# Sheet1-MCU.net
KiCad netlist of a schematic drawn in Altium Designer
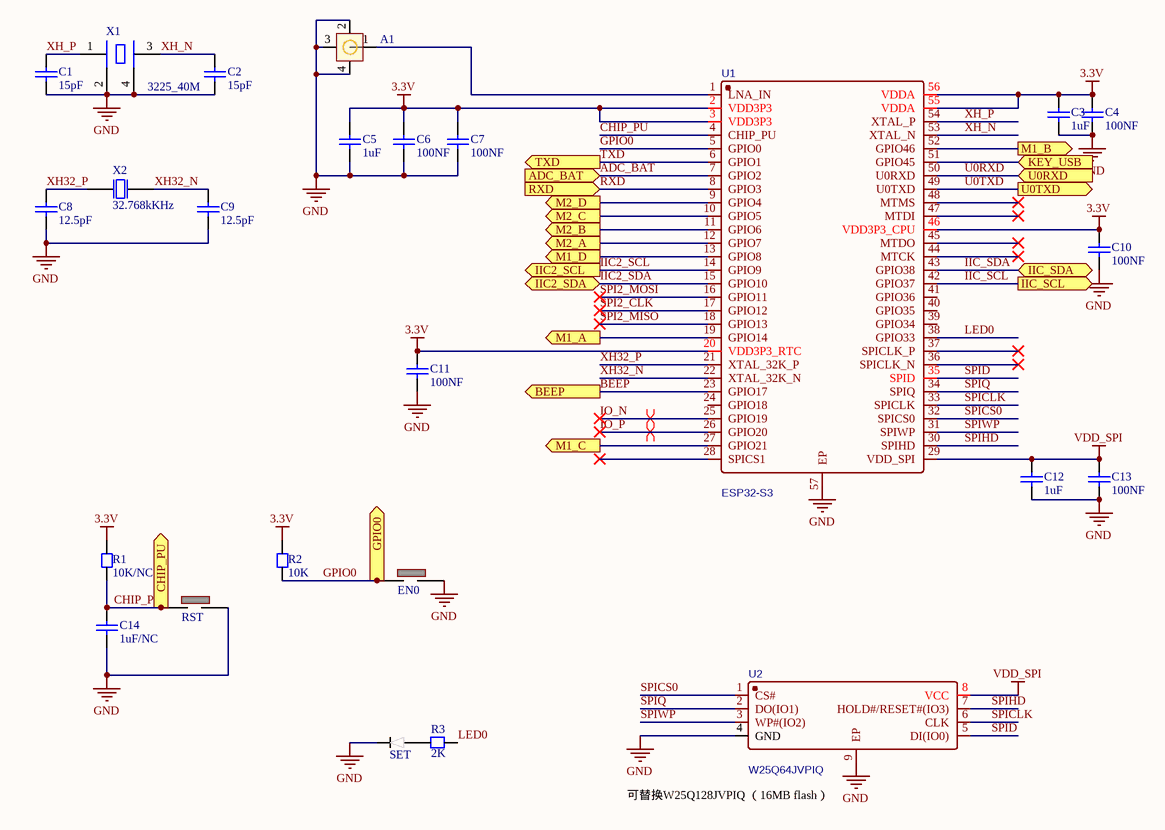
[diagram p0: Sheet1-MCU.SchDoc]

(export (version "E")
  (design (tool "Eeschema 10.0.6"))
  (components
    (comp (ref "A1")
      (value "ANT-IPEX")
      (footprint "IPEX-SMD_HC-RF-IPEX0303-01")
      (description "贴片封装的天线 封装类型为IPEX")
      (libsource (lib "antenna") (part "ANT-IPEX"))
    )
    (comp (ref "C1")
      (value "15pF")
      (footprint "CC1608-0603")
      (description "0603封装的电容")
      (fields (field (name "PUBLISHER") "Altium Limited"))
      (libsource (lib "base") (part "Cap Chip 0603"))
    )
    (comp (ref "C2")
      (value "15pF")
      (footprint "CC1608-0603")
      (description "0603封装的电容")
      (fields (field (name "PUBLISHER") "Altium Limited"))
      (libsource (lib "base") (part "Cap Chip 0603"))
    )
    (comp (ref "C3")
      (value "1uF")
      (footprint "CC1608-0603")
      (description "0603封装的电容")
      (fields (field (name "PUBLISHER") "Altium Limited"))
      (libsource (lib "base") (part "Cap Chip 0603"))
    )
    (comp (ref "C4")
      (value "100NF")
      (footprint "CC1608-0603")
      (description "0603封装的电容")
      (fields (field (name "PUBLISHER") "Altium Limited"))
      (libsource (lib "base") (part "Cap Chip 0603"))
    )
    (comp (ref "C5")
      (value "1uF")
      (footprint "CC1608-0603")
      (description "0603封装的电容")
      (fields (field (name "PUBLISHER") "Altium Limited"))
      (libsource (lib "base") (part "Cap Chip 0603"))
    )
    (comp (ref "C6")
      (value "100NF")
      (footprint "CC1608-0603")
      (description "0603封装的电容")
      (fields (field (name "PUBLISHER") "Altium Limited"))
      (libsource (lib "base") (part "Cap Chip 0603"))
    )
    (comp (ref "C7")
      (value "100NF")
      (footprint "CC1608-0603")
      (description "0603封装的电容")
      (fields (field (name "PUBLISHER") "Altium Limited"))
      (libsource (lib "base") (part "Cap Chip 0603"))
    )
    (comp (ref "C8")
      (value "12.5pF")
      (footprint "CC1608-0603")
      (description "0603封装的电容")
      (fields (field (name "PUBLISHER") "Altium Limited"))
      (libsource (lib "base") (part "Cap Chip 0603"))
    )
    (comp (ref "C9")
      (value "12.5pF")
      (footprint "CC1608-0603")
      (description "0603封装的电容")
      (fields (field (name "PUBLISHER") "Altium Limited"))
      (libsource (lib "base") (part "Cap Chip 0603"))
    )
    (comp (ref "C10")
      (value "100NF")
      (footprint "CC1608-0603")
      (description "0603封装的电容")
      (fields (field (name "PUBLISHER") "Altium Limited"))
      (libsource (lib "base") (part "Cap Chip 0603"))
    )
    (comp (ref "C11")
      (value "100NF")
      (footprint "CC1608-0603")
      (description "0603封装的电容")
      (fields (field (name "PUBLISHER") "Altium Limited"))
      (libsource (lib "base") (part "Cap Chip 0603"))
    )
    (comp (ref "C12")
      (value "1uF")
      (footprint "CC1608-0603")
      (description "0603封装的电容")
      (fields (field (name "PUBLISHER") "Altium Limited"))
      (libsource (lib "base") (part "Cap Chip 0603"))
    )
    (comp (ref "C13")
      (value "100NF")
      (footprint "CC1608-0603")
      (description "0603封装的电容")
      (fields (field (name "PUBLISHER") "Altium Limited"))
      (libsource (lib "base") (part "Cap Chip 0603"))
    )
    (comp (ref "C14")
      (value "1uF/NC")
      (footprint "CC1608-0603")
      (description "0603封装的电容")
      (fields (field (name "PUBLISHER") "Altium Limited"))
      (libsource (lib "base") (part "Cap Chip 0603"))
    )
    (comp (ref "EN0")
      (value "KEY 3*4")
      (footprint "KEY 3*4")
      (description "轻触开关按键")
      (libsource (lib "base") (part "KEY 3*4"))
    )
    (comp (ref "R1")
      (value "10K/NC")
      (footprint "CR1608-0603")
      (description "0603封装电阻")
      (fields (field (name "PUBLISHER") "Altium Limited"))
      (libsource (lib "") (part "Resistor Chip 0603_1"))
    )
    (comp (ref "R2")
      (value "10K")
      (footprint "CR1608-0603")
      (description "0603封装电阻")
      (fields (field (name "PUBLISHER") "Altium Limited"))
      (libsource (lib "") (part "Resistor Chip 0603_1"))
    )
    (comp (ref "R3")
      (value "2K")
      (footprint "CR1608-0603")
      (description "0603封装电阻")
      (fields (field (name "PUBLISHER") "Altium Limited"))
      (libsource (lib "base") (part "Resistor Chip 0603"))
    )
    (comp (ref "RST")
      (value "KEY 3*4")
      (footprint "KEY 3*4")
      (description "轻触开关按键")
      (libsource (lib "base") (part "KEY 3*4"))
    )
    (comp (ref "SET") (value "LED 0603") (footprint "LED 0603") (libsource (lib "base") (part "LED 0603")))
    (comp (ref "U1")
      (value "ESP32-S3")
      (footprint "QFN-56")
      (fields (field (name "MANUFACTURER") "ESPRESSIF(乐鑫)") (field (name "CONTRIBUTOR") "LCSC"))
      (libsource (lib "singlechip") (part "ESP32-S3"))
    )
    (comp (ref "U2")
      (value "W25Q64JVPIQ")
      (footprint "WSON-8")
      (fields
        (field (name "MANUFACTURER") "WINBOND(华邦)")
        (field (name "MANUFACTURER PART") "W25Q128JVPIQ")
        (field (name "CONTRIBUTOR") "LCSC")
      )
      (libsource (lib "PB-Chip") (part "W25Q128JVPIQ"))
    )
    (comp (ref "X1")
      (value "3225_40M")
      (footprint "XTAL-3225")
      (description "3225封装的晶振")
      (libsource (lib "base") (part "XTAL 3225"))
    )
    (comp (ref "X2")
      (value "32.768kKHz")
      (footprint "XTAL-3215")
      (description "3215封装的时钟晶振")
      (libsource (lib "base") (part "XTAL 3215 32.768kKHz"))
    )
  )
  (nets
    (net (code "1") (name "/ADC_BAT") (class "Default")
      (node (ref "U1") (pin "7") (pinfunction "GPIO2_7") (pintype "passive"))
    )
    (net (code "2") (name "/BEEP") (class "Default")
      (node (ref "U1") (pin "23") (pinfunction "GPIO17_23") (pintype "passive"))
    )
    (net (code "3") (name "/CHIP_PU") (class "Default")
      (node (ref "C14") (pin "2") (pinfunction "2_2") (pintype "passive"))
      (node (ref "R1") (pin "1") (pinfunction "1_1") (pintype "passive"))
      (node (ref "RST") (pin "1") (pinfunction "1_1") (pintype "passive"))
      (node (ref "U1") (pin "4") (pinfunction "CHIP_PU_4") (pintype "passive"))
    )
    (net (code "4") (name "/GPIO0") (class "Default")
      (node (ref "EN0") (pin "1") (pinfunction "1_1") (pintype "passive"))
      (node (ref "R2") (pin "1") (pinfunction "1_1") (pintype "passive"))
      (node (ref "U1") (pin "5") (pinfunction "GPIO0_5") (pintype "passive"))
    )
    (net (code "5") (name "/IIC2_SCL") (class "Default")
      (node (ref "U1") (pin "14") (pinfunction "GPIO9_14") (pintype "passive"))
    )
    (net (code "6") (name "/IIC2_SDA") (class "Default")
      (node (ref "U1") (pin "15") (pinfunction "GPIO10_15") (pintype "passive"))
    )
    (net (code "7") (name "/IIC_SCL") (class "Default")
      (node (ref "U1") (pin "42") (pinfunction "GPIO37_42") (pintype "passive"))
    )
    (net (code "8") (name "/IIC_SDA") (class "Default")
      (node (ref "U1") (pin "43") (pinfunction "GPIO38_43") (pintype "passive"))
    )
    (net (code "9") (name "/IO_N") (class "Default")
      (node (ref "U1") (pin "25") (pinfunction "GPIO19_25") (pintype "passive+no_connect"))
    )
    (net (code "10") (name "/IO_P") (class "Default")
      (node (ref "U1") (pin "26") (pinfunction "GPIO20_26") (pintype "passive+no_connect"))
    )
    (net (code "11") (name "/KEY_USB") (class "Default")
      (node (ref "U1") (pin "51") (pinfunction "GPIO45_51") (pintype "passive"))
    )
    (net (code "12") (name "/LED0") (class "Default")
      (node (ref "R3") (pin "1") (pinfunction "1_1") (pintype "passive"))
      (node (ref "U1") (pin "38") (pinfunction "GPIO33_38") (pintype "passive"))
    )
    (net (code "13") (name "/M1_A") (class "Default")
      (node (ref "U1") (pin "19") (pinfunction "GPIO14_19") (pintype "passive"))
    )
    (net (code "14") (name "/M1_B") (class "Default")
      (node (ref "U1") (pin "52") (pinfunction "GPIO46_52") (pintype "passive"))
    )
    (net (code "15") (name "/M1_C") (class "Default")
      (node (ref "U1") (pin "27") (pinfunction "GPIO21_27") (pintype "passive"))
    )
    (net (code "16") (name "/M1_D") (class "Default")
      (node (ref "U1") (pin "13") (pinfunction "GPIO8_13") (pintype "passive"))
    )
    (net (code "17") (name "/M2_A") (class "Default")
      (node (ref "U1") (pin "12") (pinfunction "GPIO7_12") (pintype "passive"))
    )
    (net (code "18") (name "/M2_B") (class "Default")
      (node (ref "U1") (pin "11") (pinfunction "GPIO6_11") (pintype "passive"))
    )
    (net (code "19") (name "/M2_C") (class "Default")
      (node (ref "U1") (pin "10") (pinfunction "GPIO5_10") (pintype "passive"))
    )
    (net (code "20") (name "/M2_D") (class "Default")
      (node (ref "U1") (pin "9") (pinfunction "GPIO4_9") (pintype "passive"))
    )
    (net (code "21") (name "/RXD") (class "Default")
      (node (ref "U1") (pin "8") (pinfunction "GPIO3_8") (pintype "passive"))
    )
    (net (code "22") (name "/SPI2_CLK") (class "Default")
      (node (ref "U1") (pin "17") (pinfunction "GPIO12_17") (pintype "passive+no_connect"))
    )
    (net (code "23") (name "/SPI2_MISO") (class "Default")
      (node (ref "U1") (pin "18") (pinfunction "GPIO13_18") (pintype "passive+no_connect"))
    )
    (net (code "24") (name "/SPI2_MOSI") (class "Default")
      (node (ref "U1") (pin "16") (pinfunction "GPIO11_16") (pintype "passive+no_connect"))
    )
    (net (code "25") (name "/SPICLK") (class "Default")
      (node (ref "U1") (pin "33") (pinfunction "SPICLK_33") (pintype "passive"))
      (node (ref "U2") (pin "6") (pinfunction "CLK_6") (pintype "passive"))
    )
    (net (code "26") (name "/SPICS0") (class "Default")
      (node (ref "U1") (pin "32") (pinfunction "SPICS0_32") (pintype "passive"))
      (node (ref "U2") (pin "1") (pinfunction "CS#_1") (pintype "passive"))
    )
    (net (code "27") (name "/SPID") (class "Default")
      (node (ref "U1") (pin "35") (pinfunction "SPID_35") (pintype "passive"))
      (node (ref "U2") (pin "5") (pinfunction "DI(IO0)_5") (pintype "passive"))
    )
    (net (code "28") (name "/SPIHD") (class "Default")
      (node (ref "U1") (pin "30") (pinfunction "SPIHD_30") (pintype "passive"))
      (node (ref "U2") (pin "7") (pinfunction "HOLD#/RESET#(IO3)_7") (pintype "passive"))
    )
    (net (code "29") (name "/SPIQ") (class "Default")
      (node (ref "U1") (pin "34") (pinfunction "SPIQ_34") (pintype "passive"))
      (node (ref "U2") (pin "2") (pinfunction "DO(IO1)_2") (pintype "passive"))
    )
    (net (code "30") (name "/SPIWP") (class "Default")
      (node (ref "U1") (pin "31") (pinfunction "SPIWP_31") (pintype "passive"))
      (node (ref "U2") (pin "3") (pinfunction "WP#(IO2)_3") (pintype "passive"))
    )
    (net (code "31") (name "/TXD") (class "Default")
      (node (ref "U1") (pin "6") (pinfunction "GPIO1_6") (pintype "passive"))
    )
    (net (code "32") (name "/U0RXD") (class "Default")
      (node (ref "U1") (pin "50") (pinfunction "U0RXD_50") (pintype "passive"))
    )
    (net (code "33") (name "/U0TXD") (class "Default")
      (node (ref "U1") (pin "49") (pinfunction "U0TXD_49") (pintype "passive"))
    )
    (net (code "34") (name "/XH32_N") (class "Default")
      (node (ref "C9") (pin "2") (pinfunction "2_2") (pintype "passive"))
      (node (ref "U1") (pin "22") (pinfunction "XTAL_32K_N_22") (pintype "passive"))
      (node (ref "X2") (pin "2") (pinfunction "OSC2_2") (pintype "passive"))
    )
    (net (code "35") (name "/XH32_P") (class "Default")
      (node (ref "C8") (pin "2") (pinfunction "2_2") (pintype "passive"))
      (node (ref "U1") (pin "21") (pinfunction "XTAL_32K_P_21") (pintype "passive"))
      (node (ref "X2") (pin "1") (pinfunction "OSC1_1") (pintype "passive"))
    )
    (net (code "36") (name "/XH_N") (class "Default")
      (node (ref "C2") (pin "2") (pinfunction "2_2") (pintype "passive"))
      (node (ref "U1") (pin "53") (pinfunction "XTAL_N_53") (pintype "passive"))
      (node (ref "X1") (pin "3") (pinfunction "OSC2_3") (pintype "passive"))
    )
    (net (code "37") (name "/XH_P") (class "Default")
      (node (ref "C1") (pin "2") (pinfunction "2_2") (pintype "passive"))
      (node (ref "U1") (pin "54") (pinfunction "XTAL_P_54") (pintype "passive"))
      (node (ref "X1") (pin "1") (pinfunction "OSC1_1") (pintype "passive"))
    )
    (net (code "38") (name "3.3V") (class "Default")
      (node (ref "C10") (pin "2") (pinfunction "2_2") (pintype "passive"))
      (node (ref "C11") (pin "2") (pinfunction "2_2") (pintype "passive"))
      (node (ref "C3") (pin "2") (pinfunction "2_2") (pintype "passive"))
      (node (ref "C4") (pin "2") (pinfunction "2_2") (pintype "passive"))
      (node (ref "C5") (pin "2") (pinfunction "2_2") (pintype "passive"))
      (node (ref "C6") (pin "2") (pinfunction "2_2") (pintype "passive"))
      (node (ref "C7") (pin "2") (pinfunction "2_2") (pintype "passive"))
      (node (ref "R1") (pin "2") (pinfunction "2_2") (pintype "passive"))
      (node (ref "R2") (pin "2") (pinfunction "2_2") (pintype "passive"))
      (node (ref "U1") (pin "2") (pinfunction "VDD3P3_2") (pintype "passive"))
      (node (ref "U1") (pin "20") (pinfunction "VDD3P3_RTC_20") (pintype "passive"))
      (node (ref "U1") (pin "3") (pinfunction "VDD3P3_3") (pintype "passive"))
      (node (ref "U1") (pin "46") (pinfunction "VDD3P3_CPU_46") (pintype "passive"))
      (node (ref "U1") (pin "55") (pinfunction "VDDA_55") (pintype "passive"))
      (node (ref "U1") (pin "56") (pinfunction "VDDA_56") (pintype "passive"))
    )
    (net (code "39") (name "GND") (class "Default")
      (node (ref "A1") (pin "2") (pinfunction "2_2") (pintype "passive"))
      (node (ref "A1") (pin "3") (pinfunction "3_3") (pintype "passive"))
      (node (ref "A1") (pin "4") (pinfunction "4_4") (pintype "passive"))
      (node (ref "C1") (pin "1") (pinfunction "1_1") (pintype "passive"))
      (node (ref "C10") (pin "1") (pinfunction "1_1") (pintype "passive"))
      (node (ref "C11") (pin "1") (pinfunction "1_1") (pintype "passive"))
      (node (ref "C12") (pin "1") (pinfunction "1_1") (pintype "passive"))
      (node (ref "C13") (pin "1") (pinfunction "1_1") (pintype "passive"))
      (node (ref "C14") (pin "1") (pinfunction "1_1") (pintype "passive"))
      (node (ref "C2") (pin "1") (pinfunction "1_1") (pintype "passive"))
      (node (ref "C3") (pin "1") (pinfunction "1_1") (pintype "passive"))
      (node (ref "C4") (pin "1") (pinfunction "1_1") (pintype "passive"))
      (node (ref "C5") (pin "1") (pinfunction "1_1") (pintype "passive"))
      (node (ref "C6") (pin "1") (pinfunction "1_1") (pintype "passive"))
      (node (ref "C7") (pin "1") (pinfunction "1_1") (pintype "passive"))
      (node (ref "C8") (pin "1") (pinfunction "1_1") (pintype "passive"))
      (node (ref "C9") (pin "1") (pinfunction "1_1") (pintype "passive"))
      (node (ref "EN0") (pin "2") (pinfunction "2_2") (pintype "passive"))
      (node (ref "RST") (pin "2") (pinfunction "2_2") (pintype "passive"))
      (node (ref "SET") (pin "2") (pinfunction "2_2") (pintype "passive"))
      (node (ref "U1") (pin "57") (pinfunction "EP_57") (pintype "passive"))
      (node (ref "U2") (pin "4") (pinfunction "GND_4") (pintype "passive"))
      (node (ref "U2") (pin "9") (pinfunction "EP_9") (pintype "passive"))
      (node (ref "X1") (pin "2") (pinfunction "GND_2") (pintype "passive"))
      (node (ref "X1") (pin "4") (pinfunction "GND_4") (pintype "passive"))
    )
    (net (code "40") (name "Net-(R3-Pad2)") (class "Default")
      (node (ref "R3") (pin "2") (pinfunction "2_2") (pintype "passive"))
      (node (ref "SET") (pin "1") (pinfunction "1_1") (pintype "passive"))
    )
    (net (code "41") (name "Net-(U1-LNA_IN)") (class "Default")
      (node (ref "A1") (pin "1") (pinfunction "1_1") (pintype "passive"))
      (node (ref "U1") (pin "1") (pinfunction "LNA_IN_1") (pintype "passive"))
    )
    (net (code "42") (name "VDD_SPI") (class "Default")
      (node (ref "C12") (pin "2") (pinfunction "2_2") (pintype "passive"))
      (node (ref "C13") (pin "2") (pinfunction "2_2") (pintype "passive"))
      (node (ref "U1") (pin "29") (pinfunction "VDD_SPI_29") (pintype "passive"))
      (node (ref "U2") (pin "8") (pinfunction "VCC_8") (pintype "passive"))
    )
    (net (code "43") (name "unconnected-(U1-GPIO18-Pad24)") (class "Default")
      (node (ref "U1") (pin "24") (pinfunction "GPIO18_24") (pintype "passive"))
    )
    (net (code "44") (name "unconnected-(U1-GPIO34-Pad39)") (class "Default")
      (node (ref "U1") (pin "39") (pinfunction "GPIO34_39") (pintype "passive"))
    )
    (net (code "45") (name "unconnected-(U1-GPIO35-Pad40)") (class "Default")
      (node (ref "U1") (pin "40") (pinfunction "GPIO35_40") (pintype "passive"))
    )
    (net (code "46") (name "unconnected-(U1-GPIO36-Pad41)") (class "Default")
      (node (ref "U1") (pin "41") (pinfunction "GPIO36_41") (pintype "passive"))
    )
    (net (code "47") (name "unconnected-(U1-MTCK-Pad44)") (class "Default")
      (node (ref "U1") (pin "44") (pinfunction "MTCK_44") (pintype "passive+no_connect"))
    )
    (net (code "48") (name "unconnected-(U1-MTDI-Pad47)") (class "Default")
      (node (ref "U1") (pin "47") (pinfunction "MTDI_47") (pintype "passive+no_connect"))
    )
    (net (code "49") (name "unconnected-(U1-MTDO-Pad45)") (class "Default")
      (node (ref "U1") (pin "45") (pinfunction "MTDO_45") (pintype "passive+no_connect"))
    )
    (net (code "50") (name "unconnected-(U1-MTMS-Pad48)") (class "Default")
      (node (ref "U1") (pin "48") (pinfunction "MTMS_48") (pintype "passive+no_connect"))
    )
    (net (code "51") (name "unconnected-(U1-SPICLK_N-Pad36)") (class "Default")
      (node (ref "U1") (pin "36") (pinfunction "SPICLK_N_36") (pintype "passive+no_connect"))
    )
    (net (code "52") (name "unconnected-(U1-SPICLK_P-Pad37)") (class "Default")
      (node (ref "U1") (pin "37") (pinfunction "SPICLK_P_37") (pintype "passive+no_connect"))
    )
    (net (code "53") (name "unconnected-(U1-SPICS1-Pad28)") (class "Default")
      (node (ref "U1") (pin "28") (pinfunction "SPICS1_28") (pintype "passive+no_connect"))
    )
  )
)
